# Microcontroller_Schematic.net
KiCad netlist of a schematic drawn in Altium Designer
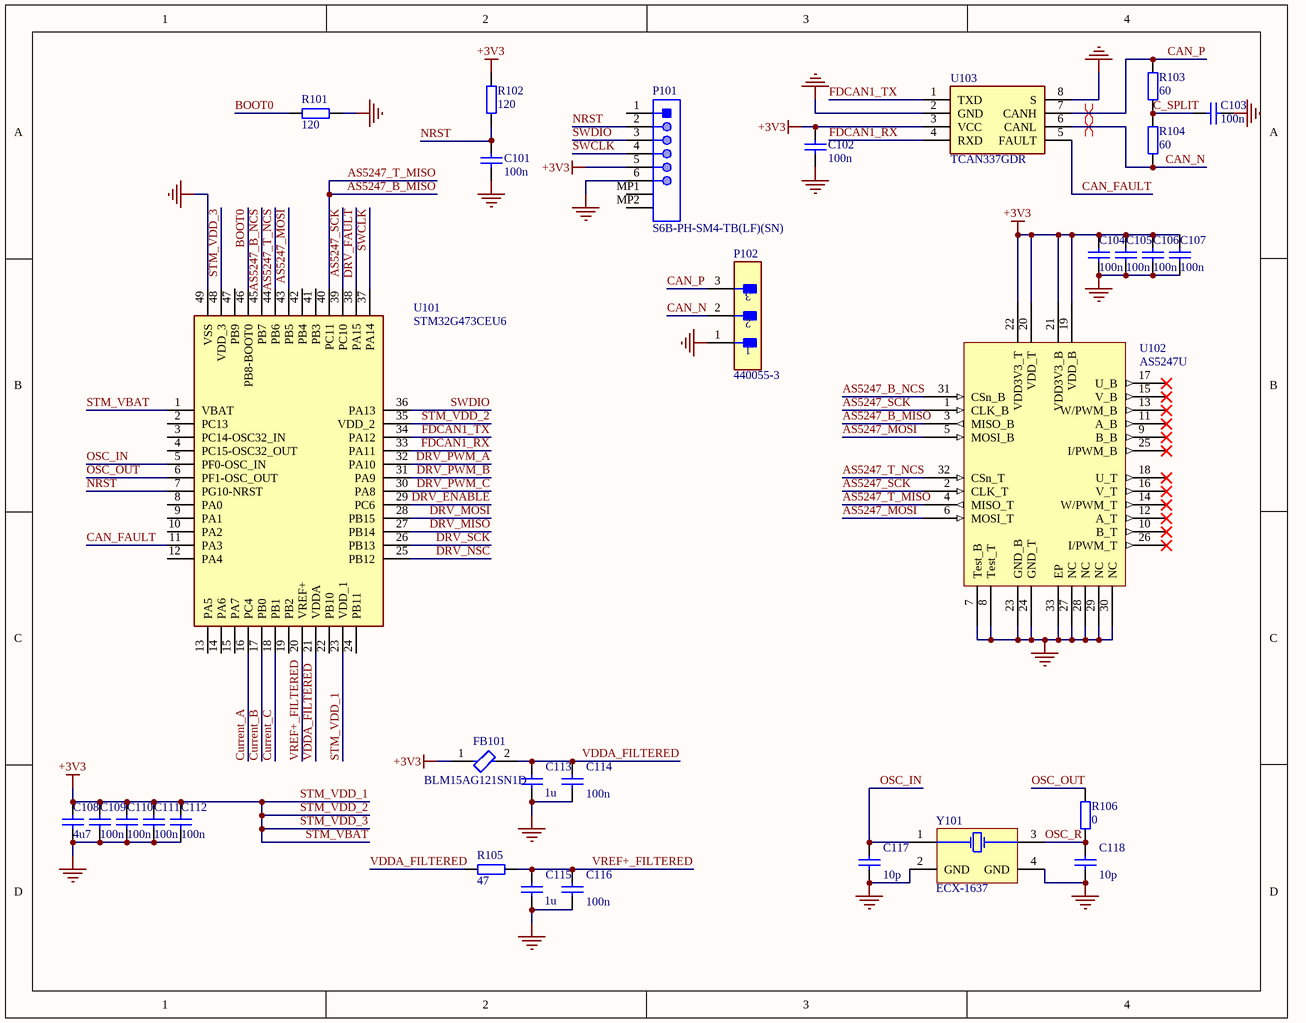
[diagram p0: Microcontroller Schematic.SchDoc]

(export (version "E")
  (design (tool "Eeschema 10.0.6"))
  (components
    (comp (ref "C101")
      (value "100n")
      (footprint "FootprintLib:CAPC1005X55N")
      (description "Capacitor")
      (fields
        (field (name "MANUFACTURER_PART_NUMBER") "CL05B104KO5NNNC")
        (field (name "MOUSER PART NUMBER") "187-CL05B104KO5NNNC")
      )
      (libsource (lib "SymbolLib") (part "CAP_0402_16V"))
    )
    (comp (ref "C102")
      (value "100n")
      (footprint "FootprintLib:CAPC1005X55N")
      (description "Capacitor")
      (fields
        (field (name "MANUFACTURER_PART_NUMBER") "CL05B104KO5NNNC")
        (field (name "MOUSER PART NUMBER") "187-CL05B104KO5NNNC")
      )
      (libsource (lib "SymbolLib") (part "CAP_0402_16V"))
    )
    (comp (ref "C103")
      (value "100n")
      (footprint "FootprintLib:CAPC1005X55N")
      (description "Capacitor")
      (fields
        (field (name "MANUFACTURER_PART_NUMBER") "CL05B104KO5NNNC")
        (field (name "MOUSER PART NUMBER") "187-CL05B104KO5NNNC")
      )
      (libsource (lib "SymbolLib") (part "CAP_0402_16V"))
    )
    (comp (ref "C104")
      (value "100n")
      (footprint "FootprintLib:CAPC1005X55N")
      (description "Capacitor")
      (fields
        (field (name "MANUFACTURER_PART_NUMBER") "CL05B104KO5NNNC")
        (field (name "MOUSER PART NUMBER") "187-CL05B104KO5NNNC")
      )
      (libsource (lib "SymbolLib") (part "CAP_0402_16V"))
    )
    (comp (ref "C105")
      (value "100n")
      (footprint "FootprintLib:CAPC1005X55N")
      (description "Capacitor")
      (fields
        (field (name "MANUFACTURER_PART_NUMBER") "CL05B104KO5NNNC")
        (field (name "MOUSER PART NUMBER") "187-CL05B104KO5NNNC")
      )
      (libsource (lib "SymbolLib") (part "CAP_0402_16V"))
    )
    (comp (ref "C106")
      (value "100n")
      (footprint "FootprintLib:CAPC1005X55N")
      (description "Capacitor")
      (fields
        (field (name "MANUFACTURER_PART_NUMBER") "CL05B104KO5NNNC")
        (field (name "MOUSER PART NUMBER") "187-CL05B104KO5NNNC")
      )
      (libsource (lib "SymbolLib") (part "CAP_0402_16V"))
    )
    (comp (ref "C107")
      (value "100n")
      (footprint "FootprintLib:CAPC1005X55N")
      (description "Capacitor")
      (fields
        (field (name "MANUFACTURER_PART_NUMBER") "CL05B104KO5NNNC")
        (field (name "MOUSER PART NUMBER") "187-CL05B104KO5NNNC")
      )
      (libsource (lib "SymbolLib") (part "CAP_0402_16V"))
    )
    (comp (ref "C108")
      (value "4u7")
      (footprint "FootprintLib:CAPC1608X90N")
      (description "Capacitor")
      (fields
        (field (name "MANUFACTURER_PART_NUMBER") "CL05B104KO5NNNC")
        (field (name "MOUSER PART NUMBER") "187-CL05B104KO5NNNC")
      )
      (libsource (lib "SymbolLib") (part "CAP_0603_16V"))
    )
    (comp (ref "C109")
      (value "100n")
      (footprint "FootprintLib:CAPC1005X55N")
      (description "Capacitor")
      (fields
        (field (name "MANUFACTURER_PART_NUMBER") "CL05B104KO5NNNC")
        (field (name "MOUSER PART NUMBER") "187-CL05B104KO5NNNC")
      )
      (libsource (lib "SymbolLib") (part "CAP_0402_16V"))
    )
    (comp (ref "C110")
      (value "100n")
      (footprint "FootprintLib:CAPC1005X55N")
      (description "Capacitor")
      (fields
        (field (name "MANUFACTURER_PART_NUMBER") "CL05B104KO5NNNC")
        (field (name "MOUSER PART NUMBER") "187-CL05B104KO5NNNC")
      )
      (libsource (lib "SymbolLib") (part "CAP_0402_16V"))
    )
    (comp (ref "C111")
      (value "100n")
      (footprint "FootprintLib:CAPC1005X55N")
      (description "Capacitor")
      (fields
        (field (name "MANUFACTURER_PART_NUMBER") "CL05B104KO5NNNC")
        (field (name "MOUSER PART NUMBER") "187-CL05B104KO5NNNC")
      )
      (libsource (lib "SymbolLib") (part "CAP_0402_16V"))
    )
    (comp (ref "C112")
      (value "100n")
      (footprint "FootprintLib:CAPC1005X55N")
      (description "Capacitor")
      (fields
        (field (name "MANUFACTURER_PART_NUMBER") "CL05B104KO5NNNC")
        (field (name "MOUSER PART NUMBER") "187-CL05B104KO5NNNC")
      )
      (libsource (lib "SymbolLib") (part "CAP_0402_16V"))
    )
    (comp (ref "C113")
      (value "1u")
      (footprint "FootprintLib:CAPC1005X55N")
      (description "Capacitor")
      (fields
        (field (name "MANUFACTURER_PART_NUMBER") "CL05B104KO5NNNC")
        (field (name "MOUSER PART NUMBER") "187-CL05B104KO5NNNC")
      )
      (libsource (lib "SymbolLib") (part "CAP_0402_16V"))
    )
    (comp (ref "C114")
      (value "100n")
      (footprint "FootprintLib:CAPC1005X55N")
      (description "Capacitor")
      (fields
        (field (name "MANUFACTURER_PART_NUMBER") "CL05B104KO5NNNC")
        (field (name "MOUSER PART NUMBER") "187-CL05B104KO5NNNC")
      )
      (libsource (lib "SymbolLib") (part "CAP_0402_16V"))
    )
    (comp (ref "C115")
      (value "1u")
      (footprint "FootprintLib:CAPC1005X55N")
      (description "Capacitor")
      (fields
        (field (name "MANUFACTURER_PART_NUMBER") "CL05B104KO5NNNC")
        (field (name "MOUSER PART NUMBER") "187-CL05B104KO5NNNC")
      )
      (libsource (lib "SymbolLib") (part "CAP_0402_16V"))
    )
    (comp (ref "C116")
      (value "100n")
      (footprint "FootprintLib:CAPC1005X55N")
      (description "Capacitor")
      (fields
        (field (name "MANUFACTURER_PART_NUMBER") "CL05B104KO5NNNC")
        (field (name "MOUSER PART NUMBER") "187-CL05B104KO5NNNC")
      )
      (libsource (lib "SymbolLib") (part "CAP_0402_16V"))
    )
    (comp (ref "C117")
      (value "10p")
      (footprint "FootprintLib:CAPC1005X55N")
      (description "Capacitor")
      (fields
        (field (name "MANUFACTURER_PART_NUMBER") "CL05B104KO5NNNC")
        (field (name "MOUSER PART NUMBER") "187-CL05B104KO5NNNC")
      )
      (libsource (lib "SymbolLib") (part "CAP_0402_16V"))
    )
    (comp (ref "C118")
      (value "10p")
      (footprint "FootprintLib:CAPC1005X55N")
      (description "Capacitor")
      (fields
        (field (name "MANUFACTURER_PART_NUMBER") "CL05B104KO5NNNC")
        (field (name "MOUSER PART NUMBER") "187-CL05B104KO5NNNC")
      )
      (libsource (lib "SymbolLib") (part "CAP_0402_16V"))
    )
    (comp (ref "FB101")
      (value "BLM15AG121SN1D")
      (footprint "FP-BLM15-0_05-MFG")
      (description "Chip Ferrite Bead, 0402, 120Ω @ 100MHz, 0.19Ω, 25%, 550mA")
      (fields (field (name "TOLERANCE") "25%"))
      (libsource (lib "Altium Content Vault") (part "5f30dd21d616792df468990f7003faa"))
    )
    (comp (ref "P101")
      (value "S6B-PH-SM4-TB(LF)(SN)")
      (footprint "JST-S6B-PH-SM4-TB(LF)(SN)_V")
      (description "Male Header, Pitch 2 mm, 1 x 6 Position, Height 5.5 mm, -25 to 85 degC")
      (fields (field (name "MANUFACTURER") "JST"))
      (libsource (lib "Altium Content Vault") (part "CN-1P-2M-R6"))
    )
    (comp (ref "P102")
      (value "440055-3")
      (footprint "FP-440055-3-MFG")
      (description "CONN HEADER R/A 3POS 2MM")
      (fields
        (field (name "MANUFACTURER") "TE Connectivity")
        (field (name "OCTOPART") "https://octopart.com/440055-3-te+connectivity-40644627")
      )
      (libsource (lib "Altium Content Vault") (part "0d3f023dd272f625e17a2be33dea85f"))
    )
    (comp (ref "R101")
      (value "120")
      (footprint "RESC1005X40N")
      (libsource (lib "SymbolLib") (part "RES_0402"))
    )
    (comp (ref "R102")
      (value "120")
      (footprint "RESC1005X40N")
      (libsource (lib "SymbolLib") (part "RES_0402"))
    )
    (comp (ref "R103")
      (value "60")
      (footprint "RESC1005X40N")
      (libsource (lib "SymbolLib") (part "RES_0402"))
    )
    (comp (ref "R104")
      (value "60")
      (footprint "RESC1005X40N")
      (libsource (lib "SymbolLib") (part "RES_0402"))
    )
    (comp (ref "R105")
      (value "47")
      (footprint "RESC1005X40N")
      (libsource (lib "SymbolLib") (part "RES_0402"))
    )
    (comp (ref "R106") (value "0") (footprint "RESC1005X40N") (libsource (lib "SymbolLib") (part "RES_0402")))
    (comp (ref "U101")
      (value "STM32G473CEU6")
      (footprint "SamacSys:QFN50P700X700X65-49N-D")
      (description "Integrated Circuit")
      (fields (field (name "MOUSER PART NUMBER") "511-STM32G473CEU6"))
      (libsource (lib "*") (part "STM32G473CEU6"))
    )
    (comp (ref "U102")
      (value "AS5247U")
      (footprint "QFN-N32-THM")
      (description "ams AS5247U Magnetic Rotary Position Sensor")
      (libsource (lib "SymbolLib") (part "AS5247U"))
    )
    (comp (ref "U103")
      (value "TCAN337GDR")
      (footprint "SamacSys:SOIC127P600X175-8N")
      (description "Integrated Circuit")
      (fields (field (name "MOUSER PART NUMBER") "595-TCAN337GDR"))
      (libsource (lib "*") (part "TCAN337GDR"))
    )
    (comp (ref "Y101")
      (value "ECX-1637")
      (footprint "ECX-1637")
      (libsource (lib "SymbolLib") (part "ECX-1637"))
    )
  )
  (nets
    (net (code "1") (name "+3V3") (class "Default")
      (node (ref "C102") (pin "2") (pinfunction "2_2") (pintype "passive"))
      (node (ref "C104") (pin "2") (pinfunction "2_2") (pintype "passive"))
      (node (ref "C105") (pin "2") (pinfunction "2_2") (pintype "passive"))
      (node (ref "C106") (pin "2") (pinfunction "2_2") (pintype "passive"))
      (node (ref "C107") (pin "2") (pinfunction "2_2") (pintype "passive"))
      (node (ref "C108") (pin "1") (pinfunction "1_1") (pintype "passive"))
      (node (ref "C109") (pin "2") (pinfunction "2_2") (pintype "passive"))
      (node (ref "C110") (pin "2") (pinfunction "2_2") (pintype "passive"))
      (node (ref "C111") (pin "2") (pinfunction "2_2") (pintype "passive"))
      (node (ref "C112") (pin "2") (pinfunction "2_2") (pintype "passive"))
      (node (ref "FB101") (pin "1") (pinfunction "1_1") (pintype "passive"))
      (node (ref "P101") (pin "5") (pinfunction "5_5") (pintype "passive"))
      (node (ref "R102") (pin "1") (pinfunction "1_1") (pintype "passive"))
      (node (ref "U101") (pin "1") (pinfunction "VBAT_1") (pintype "passive"))
      (node (ref "U101") (pin "23") (pinfunction "VDD_1_23") (pintype "passive"))
      (node (ref "U101") (pin "35") (pinfunction "VDD_2_35") (pintype "passive"))
      (node (ref "U101") (pin "48") (pinfunction "VDD_3_48") (pintype "passive"))
      (node (ref "U102") (pin "19") (pinfunction "VDD_B_19") (pintype "power_in"))
      (node (ref "U102") (pin "20") (pinfunction "VDD_T_20") (pintype "power_in"))
      (node (ref "U102") (pin "21") (pinfunction "VDD3V3_B_21") (pintype "power_in"))
      (node (ref "U102") (pin "22") (pinfunction "VDD3V3_T_22") (pintype "power_in"))
      (node (ref "U103") (pin "3") (pinfunction "VCC_3") (pintype "passive"))
    )
    (net (code "2") (name "/AS5247_B_MISO") (class "Default")
      (node (ref "U101") (pin "40") (pinfunction "PC11_40") (pintype "passive"))
      (node (ref "U102") (pin "3") (pinfunction "MISO_B_3") (pintype "output"))
      (node (ref "U102") (pin "4") (pinfunction "MISO_T_4") (pintype "output"))
    )
    (net (code "3") (name "/AS5247_B_NCS") (class "Default")
      (node (ref "U101") (pin "45") (pinfunction "PB7_45") (pintype "passive"))
      (node (ref "U102") (pin "31") (pinfunction "CSn_B_31") (pintype "input"))
    )
    (net (code "4") (name "/AS5247_MOSI") (class "Default")
      (node (ref "U101") (pin "43") (pinfunction "PB5_43") (pintype "passive"))
      (node (ref "U102") (pin "5") (pinfunction "MOSI_B_5") (pintype "input"))
      (node (ref "U102") (pin "6") (pinfunction "MOSI_T_6") (pintype "input"))
    )
    (net (code "5") (name "/AS5247_SCK") (class "Default")
      (node (ref "U101") (pin "39") (pinfunction "PC10_39") (pintype "passive"))
      (node (ref "U102") (pin "1") (pinfunction "CLK_B_1") (pintype "input"))
      (node (ref "U102") (pin "2") (pinfunction "CLK_T_2") (pintype "input"))
    )
    (net (code "6") (name "/AS5247_T_NCS") (class "Default")
      (node (ref "U101") (pin "44") (pinfunction "PB6_44") (pintype "passive"))
      (node (ref "U102") (pin "32") (pinfunction "CSn_T_32") (pintype "input"))
    )
    (net (code "7") (name "/BOOT0") (class "Default")
      (node (ref "R101") (pin "1") (pinfunction "1_1") (pintype "passive"))
      (node (ref "U101") (pin "46") (pinfunction "PB8-BOOT0_46") (pintype "passive"))
    )
    (net (code "8") (name "/CAN_FAULT") (class "Default")
      (node (ref "U101") (pin "11") (pinfunction "PA3_11") (pintype "passive"))
      (node (ref "U103") (pin "5") (pinfunction "FAULT_5") (pintype "passive"))
    )
    (net (code "9") (name "/CAN_N") (class "Default")
      (node (ref "P102") (pin "2") (pinfunction "2_2") (pintype "passive"))
      (node (ref "R104") (pin "1") (pinfunction "1_1") (pintype "passive"))
      (node (ref "U103") (pin "6") (pinfunction "CANL_6") (pintype "passive"))
    )
    (net (code "10") (name "/CAN_P") (class "Default")
      (node (ref "P102") (pin "3") (pinfunction "3_3") (pintype "passive"))
      (node (ref "R103") (pin "2") (pinfunction "2_2") (pintype "passive"))
      (node (ref "U103") (pin "7") (pinfunction "CANH_7") (pintype "passive"))
    )
    (net (code "11") (name "/C_SPLIT") (class "Default")
      (node (ref "C103") (pin "1") (pinfunction "1_1") (pintype "passive"))
      (node (ref "R103") (pin "1") (pinfunction "1_1") (pintype "passive"))
      (node (ref "R104") (pin "2") (pinfunction "2_2") (pintype "passive"))
    )
    (net (code "12") (name "/Current_A") (class "Default")
      (node (ref "U101") (pin "16") (pinfunction "PC4_16") (pintype "passive"))
    )
    (net (code "13") (name "/Current_B") (class "Default")
      (node (ref "U101") (pin "17") (pinfunction "PB0_17") (pintype "passive"))
    )
    (net (code "14") (name "/Current_C") (class "Default")
      (node (ref "U101") (pin "18") (pinfunction "PB1_18") (pintype "passive"))
    )
    (net (code "15") (name "/DRV_ENABLE") (class "Default")
      (node (ref "U101") (pin "29") (pinfunction "PC6_29") (pintype "passive"))
    )
    (net (code "16") (name "/DRV_FAULT") (class "Default")
      (node (ref "U101") (pin "38") (pinfunction "PA15_38") (pintype "passive"))
    )
    (net (code "17") (name "/DRV_MISO") (class "Default")
      (node (ref "U101") (pin "27") (pinfunction "PB14_27") (pintype "passive"))
    )
    (net (code "18") (name "/DRV_MOSI") (class "Default")
      (node (ref "U101") (pin "28") (pinfunction "PB15_28") (pintype "passive"))
    )
    (net (code "19") (name "/DRV_NSC") (class "Default")
      (node (ref "U101") (pin "25") (pinfunction "PB12_25") (pintype "passive"))
    )
    (net (code "20") (name "/DRV_PWM_A") (class "Default")
      (node (ref "U101") (pin "32") (pinfunction "PA10_32") (pintype "passive"))
    )
    (net (code "21") (name "/DRV_PWM_B") (class "Default")
      (node (ref "U101") (pin "31") (pinfunction "PA9_31") (pintype "passive"))
    )
    (net (code "22") (name "/DRV_PWM_C") (class "Default")
      (node (ref "U101") (pin "30") (pinfunction "PA8_30") (pintype "passive"))
    )
    (net (code "23") (name "/DRV_SCK") (class "Default")
      (node (ref "U101") (pin "26") (pinfunction "PB13_26") (pintype "passive"))
    )
    (net (code "24") (name "/FDCAN1_RX") (class "Default")
      (node (ref "U101") (pin "33") (pinfunction "PA11_33") (pintype "passive"))
      (node (ref "U103") (pin "4") (pinfunction "RXD_4") (pintype "passive"))
    )
    (net (code "25") (name "/FDCAN1_TX") (class "Default")
      (node (ref "U101") (pin "34") (pinfunction "PA12_34") (pintype "passive"))
      (node (ref "U103") (pin "1") (pinfunction "TXD_1") (pintype "passive"))
    )
    (net (code "26") (name "/NRST") (class "Default")
      (node (ref "C101") (pin "1") (pinfunction "1_1") (pintype "passive"))
      (node (ref "P101") (pin "2") (pinfunction "2_2") (pintype "passive"))
      (node (ref "R102") (pin "2") (pinfunction "2_2") (pintype "passive"))
      (node (ref "U101") (pin "7") (pinfunction "PG10-NRST_7") (pintype "passive"))
    )
    (net (code "27") (name "/OSC_IN") (class "Default")
      (node (ref "C117") (pin "2") (pinfunction "2_2") (pintype "passive"))
      (node (ref "U101") (pin "5") (pinfunction "PF0-OSC_IN_5") (pintype "passive"))
      (node (ref "Y101") (pin "1") (pinfunction "X1_1") (pintype "passive"))
    )
    (net (code "28") (name "/OSC_OUT") (class "Default")
      (node (ref "R106") (pin "1") (pinfunction "1_1") (pintype "passive"))
      (node (ref "U101") (pin "6") (pinfunction "PF1-OSC_OUT_6") (pintype "passive"))
    )
    (net (code "29") (name "/OSC_R") (class "Default")
      (node (ref "C118") (pin "2") (pinfunction "2_2") (pintype "passive"))
      (node (ref "R106") (pin "2") (pinfunction "2_2") (pintype "passive"))
      (node (ref "Y101") (pin "3") (pinfunction "X2_3") (pintype "passive"))
    )
    (net (code "30") (name "/SWCLK") (class "Default")
      (node (ref "P101") (pin "4") (pinfunction "4_4") (pintype "passive"))
      (node (ref "U101") (pin "37") (pinfunction "PA14_37") (pintype "passive"))
    )
    (net (code "31") (name "/SWDIO") (class "Default")
      (node (ref "P101") (pin "3") (pinfunction "3_3") (pintype "passive"))
      (node (ref "U101") (pin "36") (pinfunction "PA13_36") (pintype "passive"))
    )
    (net (code "32") (name "/VDDA_FILTERED") (class "Default")
      (node (ref "C113") (pin "2") (pinfunction "2_2") (pintype "passive"))
      (node (ref "C114") (pin "2") (pinfunction "2_2") (pintype "passive"))
      (node (ref "FB101") (pin "2") (pinfunction "2_2") (pintype "passive"))
      (node (ref "R105") (pin "1") (pinfunction "1_1") (pintype "passive"))
      (node (ref "U101") (pin "21") (pinfunction "VDDA_21") (pintype "passive"))
    )
    (net (code "33") (name "/VREF+_FILTERED") (class "Default")
      (node (ref "C115") (pin "2") (pinfunction "2_2") (pintype "passive"))
      (node (ref "C116") (pin "2") (pinfunction "2_2") (pintype "passive"))
      (node (ref "R105") (pin "2") (pinfunction "2_2") (pintype "passive"))
      (node (ref "U101") (pin "20") (pinfunction "VREF+_20") (pintype "passive"))
    )
    (net (code "34") (name "GND") (class "Default")
      (node (ref "C101") (pin "2") (pinfunction "2_2") (pintype "passive"))
      (node (ref "C102") (pin "1") (pinfunction "1_1") (pintype "passive"))
      (node (ref "C103") (pin "2") (pinfunction "2_2") (pintype "passive"))
      (node (ref "C104") (pin "1") (pinfunction "1_1") (pintype "passive"))
      (node (ref "C105") (pin "1") (pinfunction "1_1") (pintype "passive"))
      (node (ref "C106") (pin "1") (pinfunction "1_1") (pintype "passive"))
      (node (ref "C107") (pin "1") (pinfunction "1_1") (pintype "passive"))
      (node (ref "C108") (pin "2") (pinfunction "2_2") (pintype "passive"))
      (node (ref "C109") (pin "1") (pinfunction "1_1") (pintype "passive"))
      (node (ref "C110") (pin "1") (pinfunction "1_1") (pintype "passive"))
      (node (ref "C111") (pin "1") (pinfunction "1_1") (pintype "passive"))
      (node (ref "C112") (pin "1") (pinfunction "1_1") (pintype "passive"))
      (node (ref "C113") (pin "1") (pinfunction "1_1") (pintype "passive"))
      (node (ref "C114") (pin "1") (pinfunction "1_1") (pintype "passive"))
      (node (ref "C115") (pin "1") (pinfunction "1_1") (pintype "passive"))
      (node (ref "C116") (pin "1") (pinfunction "1_1") (pintype "passive"))
      (node (ref "C117") (pin "1") (pinfunction "1_1") (pintype "passive"))
      (node (ref "C118") (pin "1") (pinfunction "1_1") (pintype "passive"))
      (node (ref "P101") (pin "6") (pinfunction "6_6") (pintype "passive"))
      (node (ref "P102") (pin "1") (pinfunction "1_1") (pintype "passive"))
      (node (ref "R101") (pin "2") (pinfunction "2_2") (pintype "passive"))
      (node (ref "U101") (pin "49") (pinfunction "VSS_49") (pintype "passive"))
      (node (ref "U102") (pin "23") (pinfunction "GND_B_23") (pintype "power_in"))
      (node (ref "U102") (pin "24") (pinfunction "GND_T_24") (pintype "power_in"))
      (node (ref "U102") (pin "27") (pinfunction "NC_27") (pintype "passive"))
      (node (ref "U102") (pin "28") (pinfunction "NC_28") (pintype "passive"))
      (node (ref "U102") (pin "29") (pinfunction "NC_29") (pintype "passive"))
      (node (ref "U102") (pin "30") (pinfunction "NC_30") (pintype "passive"))
      (node (ref "U102") (pin "33") (pinfunction "EP_33") (pintype "passive"))
      (node (ref "U102") (pin "7") (pinfunction "Test_B_7") (pintype "power_in"))
      (node (ref "U102") (pin "8") (pinfunction "Test_T_8") (pintype "power_in"))
      (node (ref "U103") (pin "2") (pinfunction "GND_2") (pintype "passive"))
      (node (ref "U103") (pin "8") (pinfunction "S_8") (pintype "passive"))
      (node (ref "Y101") (pin "2") (pinfunction "GND_2") (pintype "power_in"))
      (node (ref "Y101") (pin "4") (pinfunction "GND_4") (pintype "power_in"))
    )
    (net (code "35") (name "unconnected-(P101-Pad1)") (class "Default")
      (node (ref "P101") (pin "1") (pinfunction "1_1") (pintype "passive"))
    )
    (net (code "36") (name "unconnected-(P101-PadMP1)") (class "Default")
      (node (ref "P101") (pin "MP1") (pinfunction "MP1_MP1") (pintype "passive"))
    )
    (net (code "37") (name "unconnected-(P101-PadMP2)") (class "Default")
      (node (ref "P101") (pin "MP2") (pinfunction "MP2_MP2") (pintype "passive"))
    )
    (net (code "38") (name "unconnected-(U101-PA0-Pad8)") (class "Default")
      (node (ref "U101") (pin "8") (pinfunction "PA0_8") (pintype "passive"))
    )
    (net (code "39") (name "unconnected-(U101-PA1-Pad9)") (class "Default")
      (node (ref "U101") (pin "9") (pinfunction "PA1_9") (pintype "passive"))
    )
    (net (code "40") (name "unconnected-(U101-PA2-Pad10)") (class "Default")
      (node (ref "U101") (pin "10") (pinfunction "PA2_10") (pintype "passive"))
    )
    (net (code "41") (name "unconnected-(U101-PA4-Pad12)") (class "Default")
      (node (ref "U101") (pin "12") (pinfunction "PA4_12") (pintype "passive"))
    )
    (net (code "42") (name "unconnected-(U101-PA5-Pad13)") (class "Default")
      (node (ref "U101") (pin "13") (pinfunction "PA5_13") (pintype "passive"))
    )
    (net (code "43") (name "unconnected-(U101-PA6-Pad14)") (class "Default")
      (node (ref "U101") (pin "14") (pinfunction "PA6_14") (pintype "passive"))
    )
    (net (code "44") (name "unconnected-(U101-PA7-Pad15)") (class "Default")
      (node (ref "U101") (pin "15") (pinfunction "PA7_15") (pintype "passive"))
    )
    (net (code "45") (name "unconnected-(U101-PB2-Pad19)") (class "Default")
      (node (ref "U101") (pin "19") (pinfunction "PB2_19") (pintype "passive"))
    )
    (net (code "46") (name "unconnected-(U101-PB3-Pad41)") (class "Default")
      (node (ref "U101") (pin "41") (pinfunction "PB3_41") (pintype "passive"))
    )
    (net (code "47") (name "unconnected-(U101-PB4-Pad42)") (class "Default")
      (node (ref "U101") (pin "42") (pinfunction "PB4_42") (pintype "passive"))
    )
    (net (code "48") (name "unconnected-(U101-PB9-Pad47)") (class "Default")
      (node (ref "U101") (pin "47") (pinfunction "PB9_47") (pintype "passive"))
    )
    (net (code "49") (name "unconnected-(U101-PB10-Pad22)") (class "Default")
      (node (ref "U101") (pin "22") (pinfunction "PB10_22") (pintype "passive"))
    )
    (net (code "50") (name "unconnected-(U101-PB11-Pad24)") (class "Default")
      (node (ref "U101") (pin "24") (pinfunction "PB11_24") (pintype "passive"))
    )
    (net (code "51") (name "unconnected-(U101-PC13-Pad2)") (class "Default")
      (node (ref "U101") (pin "2") (pinfunction "PC13_2") (pintype "passive"))
    )
    (net (code "52") (name "unconnected-(U101-PC14-OSC32_IN-Pad3)") (class "Default")
      (node (ref "U101") (pin "3") (pinfunction "PC14-OSC32_IN_3") (pintype "passive"))
    )
    (net (code "53") (name "unconnected-(U101-PC15-OSC32_OUT-Pad4)") (class "Default")
      (node (ref "U101") (pin "4") (pinfunction "PC15-OSC32_OUT_4") (pintype "passive"))
    )
    (net (code "54") (name "unconnected-(U102-A_B-Pad11)") (class "Default")
      (node (ref "U102") (pin "11") (pinfunction "A_B_11") (pintype "output+no_connect"))
    )
    (net (code "55") (name "unconnected-(U102-A_T-Pad12)") (class "Default")
      (node (ref "U102") (pin "12") (pinfunction "A_T_12") (pintype "output+no_connect"))
    )
    (net (code "56") (name "unconnected-(U102-B_B-Pad9)") (class "Default")
      (node (ref "U102") (pin "9") (pinfunction "B_B_9") (pintype "output+no_connect"))
    )
    (net (code "57") (name "unconnected-(U102-B_T-Pad10)") (class "Default")
      (node (ref "U102") (pin "10") (pinfunction "B_T_10") (pintype "output+no_connect"))
    )
    (net (code "58") (name "unconnected-(U102-I{slash}PWM_B-Pad25)") (class "Default")
      (node (ref "U102") (pin "25") (pinfunction "I/PWM_B_25") (pintype "output+no_connect"))
    )
    (net (code "59") (name "unconnected-(U102-I{slash}PWM_T-Pad26)") (class "Default")
      (node (ref "U102") (pin "26") (pinfunction "I/PWM_T_26") (pintype "output+no_connect"))
    )
    (net (code "60") (name "unconnected-(U102-U_B-Pad17)") (class "Default")
      (node (ref "U102") (pin "17") (pinfunction "U_B_17") (pintype "output+no_connect"))
    )
    (net (code "61") (name "unconnected-(U102-U_T-Pad18)") (class "Default")
      (node (ref "U102") (pin "18") (pinfunction "U_T_18") (pintype "output+no_connect"))
    )
    (net (code "62") (name "unconnected-(U102-V_B-Pad15)") (class "Default")
      (node (ref "U102") (pin "15") (pinfunction "V_B_15") (pintype "output+no_connect"))
    )
    (net (code "63") (name "unconnected-(U102-V_T-Pad16)") (class "Default")
      (node (ref "U102") (pin "16") (pinfunction "V_T_16") (pintype "output+no_connect"))
    )
    (net (code "64") (name "unconnected-(U102-W{slash}PWM_B-Pad13)") (class "Default")
      (node (ref "U102") (pin "13") (pinfunction "W/PWM_B_13") (pintype "output+no_connect"))
    )
    (net (code "65") (name "unconnected-(U102-W{slash}PWM_T-Pad14)") (class "Default")
      (node (ref "U102") (pin "14") (pinfunction "W/PWM_T_14") (pintype "output+no_connect"))
    )
  )
)
